# CH340T9R-R0.net
KiCad netlist of a schematic drawn in Altium Designer
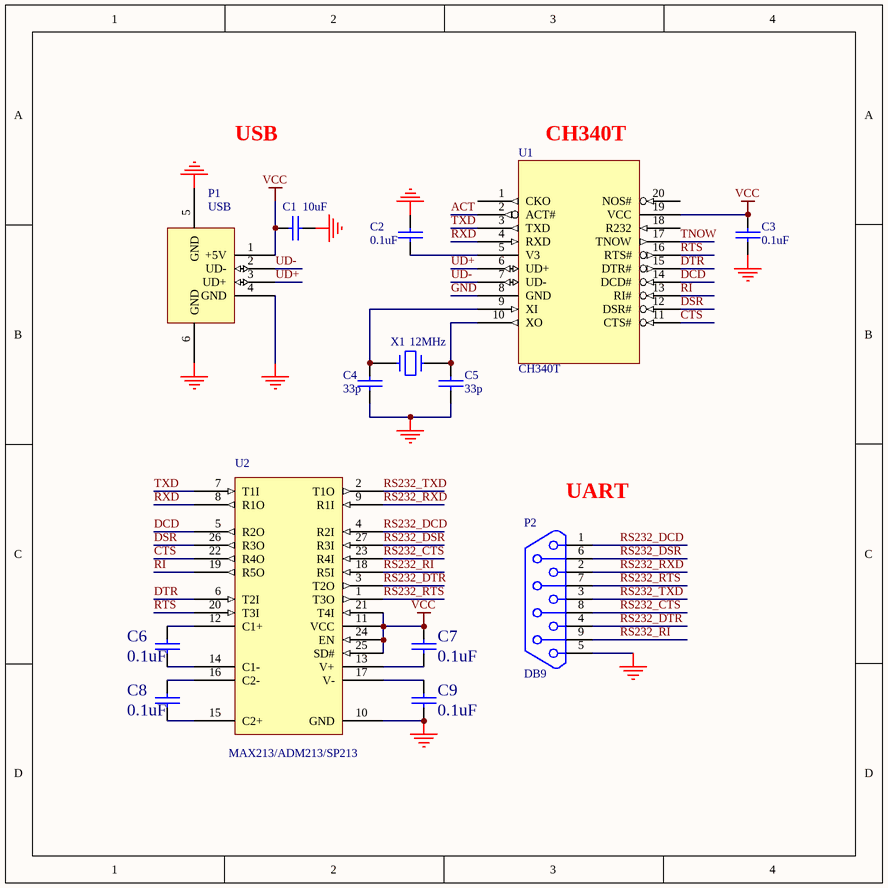
[diagram p0: CH340T9R-R0.SchDoc]

(export (version "E")
  (design (tool "Eeschema 10.0.6"))
  (components
    (comp (ref "C1")
      (value "10uF")
      (footprint "3216_C")
      (description "Capacitor")
      (libsource (lib "") (part "CAP_1"))
    )
    (comp (ref "C2")
      (value "0.1uF")
      (footprint "0603_C")
      (description "Capacitor")
      (libsource (lib "") (part "CAP_1"))
    )
    (comp (ref "C3")
      (value "0.1uF")
      (footprint "0603_C")
      (description "Capacitor")
      (libsource (lib "") (part "CAP_1"))
    )
    (comp (ref "C4")
      (value "33p")
      (footprint "0603_C")
      (description "Capacitor")
      (libsource (lib "*") (part "CAP"))
    )
    (comp (ref "C5")
      (value "33p")
      (footprint "0603_C")
      (description "Capacitor")
      (libsource (lib "*") (part "CAP"))
    )
    (comp (ref "C6")
      (value "0.1uF")
      (footprint "0603_C")
      (description "Capacitor")
      (libsource (lib "*") (part "CAP"))
    )
    (comp (ref "C7")
      (value "0.1uF")
      (footprint "0603_C")
      (description "Capacitor")
      (libsource (lib "*") (part "CAP"))
    )
    (comp (ref "C8")
      (value "0.1uF")
      (footprint "0603_C")
      (description "Capacitor")
      (libsource (lib "*") (part "CAP"))
    )
    (comp (ref "C9")
      (value "0.1uF")
      (footprint "0603_C")
      (description "Capacitor")
      (libsource (lib "*") (part "CAP"))
    )
    (comp (ref "P1") (value "USB") (footprint "USBAM") (libsource (lib "*") (part "USB")))
    (comp (ref "P2") (value "DB9") (footprint "DB9-PAD-M") (libsource (lib "*") (part "DB9")))
    (comp (ref "U1")
      (value "CH340T")
      (footprint "SSOP20")
      (description "USB to TTL Serial / UART,  USB to IrDA")
      (libsource (lib "CHXXX") (part "CH340T"))
    )
    (comp (ref "U2") (value "MAX213/ADM213/SP213") (footprint "SSOP28") (libsource (lib "*") (part "MAX213")))
    (comp (ref "X1")
      (value "12MHz")
      (footprint "XT3225")
      (description "Crystal")
      (libsource (lib "*") (part "CRYSTAL"))
    )
  )
  (nets
    (net (code "1") (name "/ACT") (class "Default")
      (node (ref "U1") (pin "2") (pinfunction "ACT#_2") (pintype "output"))
    )
    (net (code "2") (name "/CTS") (class "Default")
      (node (ref "U1") (pin "11") (pinfunction "CTS#_11") (pintype "input"))
      (node (ref "U2") (pin "22") (pinfunction "R4O_22") (pintype "output"))
    )
    (net (code "3") (name "/DCD") (class "Default")
      (node (ref "U1") (pin "14") (pinfunction "DCD#_14") (pintype "input"))
      (node (ref "U2") (pin "5") (pinfunction "R2O_5") (pintype "output"))
    )
    (net (code "4") (name "/DSR") (class "Default")
      (node (ref "U1") (pin "12") (pinfunction "DSR#_12") (pintype "input"))
      (node (ref "U2") (pin "26") (pinfunction "R3O_26") (pintype "output"))
    )
    (net (code "5") (name "/DTR") (class "Default")
      (node (ref "U1") (pin "15") (pinfunction "DTR#_15") (pintype "output"))
      (node (ref "U2") (pin "6") (pinfunction "T2I_6") (pintype "input"))
    )
    (net (code "6") (name "/RI") (class "Default")
      (node (ref "U1") (pin "13") (pinfunction "RI#_13") (pintype "input"))
      (node (ref "U2") (pin "19") (pinfunction "R5O_19") (pintype "output"))
    )
    (net (code "7") (name "/RS232_CTS") (class "Default")
      (node (ref "P2") (pin "8") (pinfunction "8_8") (pintype "passive"))
      (node (ref "U2") (pin "23") (pinfunction "R4I_23") (pintype "input"))
    )
    (net (code "8") (name "/RS232_DCD") (class "Default")
      (node (ref "P2") (pin "1") (pinfunction "1_1") (pintype "passive"))
      (node (ref "U2") (pin "4") (pinfunction "R2I_4") (pintype "input"))
    )
    (net (code "9") (name "/RS232_DSR") (class "Default")
      (node (ref "P2") (pin "6") (pinfunction "6_6") (pintype "passive"))
      (node (ref "U2") (pin "27") (pinfunction "R3I_27") (pintype "input"))
    )
    (net (code "10") (name "/RS232_DTR") (class "Default")
      (node (ref "P2") (pin "4") (pinfunction "4_4") (pintype "passive"))
      (node (ref "U2") (pin "3") (pinfunction "T2O_3") (pintype "output"))
    )
    (net (code "11") (name "/RS232_RI") (class "Default")
      (node (ref "P2") (pin "9") (pinfunction "9_9") (pintype "passive"))
      (node (ref "U2") (pin "18") (pinfunction "R5I_18") (pintype "input"))
    )
    (net (code "12") (name "/RS232_RTS") (class "Default")
      (node (ref "P2") (pin "7") (pinfunction "7_7") (pintype "passive"))
      (node (ref "U2") (pin "1") (pinfunction "T3O_1") (pintype "output"))
    )
    (net (code "13") (name "/RS232_RXD") (class "Default")
      (node (ref "P2") (pin "2") (pinfunction "2_2") (pintype "passive"))
      (node (ref "U2") (pin "9") (pinfunction "R1I_9") (pintype "input"))
    )
    (net (code "14") (name "/RS232_TXD") (class "Default")
      (node (ref "P2") (pin "3") (pinfunction "3_3") (pintype "passive"))
      (node (ref "U2") (pin "2") (pinfunction "T1O_2") (pintype "output"))
    )
    (net (code "15") (name "/RTS") (class "Default")
      (node (ref "U1") (pin "16") (pinfunction "RTS#_16") (pintype "output"))
      (node (ref "U2") (pin "20") (pinfunction "T3I_20") (pintype "input"))
    )
    (net (code "16") (name "/RXD") (class "Default")
      (node (ref "U1") (pin "4") (pinfunction "RXD_4") (pintype "input"))
      (node (ref "U2") (pin "8") (pinfunction "R1O_8") (pintype "output"))
    )
    (net (code "17") (name "/TNOW") (class "Default")
      (node (ref "U1") (pin "17") (pinfunction "TNOW_17") (pintype "output"))
    )
    (net (code "18") (name "/TXD") (class "Default")
      (node (ref "U1") (pin "3") (pinfunction "TXD_3") (pintype "output"))
      (node (ref "U2") (pin "7") (pinfunction "T1I_7") (pintype "input"))
    )
    (net (code "19") (name "/UD+") (class "Default")
      (node (ref "P1") (pin "3") (pinfunction "UD+_3") (pintype "bidirectional"))
      (node (ref "U1") (pin "6") (pinfunction "UD+_6") (pintype "bidirectional"))
    )
    (net (code "20") (name "/UD-") (class "Default")
      (node (ref "P1") (pin "2") (pinfunction "UD-_2") (pintype "bidirectional"))
      (node (ref "U1") (pin "7") (pinfunction "UD-_7") (pintype "bidirectional"))
    )
    (net (code "21") (name "GND") (class "Default")
      (node (ref "C1") (pin "2") (pinfunction "2_2") (pintype "passive"))
      (node (ref "C2") (pin "2") (pinfunction "2_2") (pintype "passive"))
      (node (ref "C3") (pin "2") (pinfunction "2_2") (pintype "passive"))
      (node (ref "C4") (pin "2") (pinfunction "2_2") (pintype "passive"))
      (node (ref "C5") (pin "2") (pinfunction "2_2") (pintype "passive"))
      (node (ref "C9") (pin "2") (pinfunction "2_2") (pintype "passive"))
      (node (ref "P1") (pin "4") (pinfunction "GND_4") (pintype "power_in"))
      (node (ref "P1") (pin "5") (pinfunction "GND_5") (pintype "power_in"))
      (node (ref "P1") (pin "6") (pinfunction "GND_6") (pintype "power_in"))
      (node (ref "P2") (pin "5") (pinfunction "5_5") (pintype "passive"))
      (node (ref "U1") (pin "8") (pinfunction "GND_8") (pintype "power_in"))
      (node (ref "U2") (pin "10") (pinfunction "GND_10") (pintype "power_in"))
    )
    (net (code "22") (name "Net-(U1-V3)") (class "Default")
      (node (ref "C2") (pin "1") (pinfunction "1_1") (pintype "passive"))
      (node (ref "U1") (pin "5") (pinfunction "V3_5") (pintype "power_in"))
    )
    (net (code "23") (name "Net-(U1-XI)") (class "Default")
      (node (ref "C4") (pin "1") (pinfunction "1_1") (pintype "passive"))
      (node (ref "U1") (pin "9") (pinfunction "XI_9") (pintype "input"))
      (node (ref "X1") (pin "1") (pinfunction "1_1") (pintype "passive"))
    )
    (net (code "24") (name "Net-(U1-XO)") (class "Default")
      (node (ref "C5") (pin "1") (pinfunction "1_1") (pintype "passive"))
      (node (ref "U1") (pin "10") (pinfunction "XO_10") (pintype "output"))
      (node (ref "X1") (pin "3") (pinfunction "3_3") (pintype "passive"))
    )
    (net (code "25") (name "Net-(U2-C1+)") (class "Default")
      (node (ref "C6") (pin "1") (pinfunction "1_1") (pintype "passive"))
      (node (ref "U2") (pin "12") (pinfunction "C1+_12") (pintype "passive"))
    )
    (net (code "26") (name "Net-(U2-C1-)") (class "Default")
      (node (ref "C6") (pin "2") (pinfunction "2_2") (pintype "passive"))
      (node (ref "U2") (pin "14") (pinfunction "C1-_14") (pintype "passive"))
    )
    (net (code "27") (name "Net-(U2-C2+)") (class "Default")
      (node (ref "C8") (pin "2") (pinfunction "2_2") (pintype "passive"))
      (node (ref "U2") (pin "15") (pinfunction "C2+_15") (pintype "passive"))
    )
    (net (code "28") (name "Net-(U2-C2-)") (class "Default")
      (node (ref "C8") (pin "1") (pinfunction "1_1") (pintype "passive"))
      (node (ref "U2") (pin "16") (pinfunction "C2-_16") (pintype "passive"))
    )
    (net (code "29") (name "Net-(U2-V+)") (class "Default")
      (node (ref "C7") (pin "2") (pinfunction "2_2") (pintype "passive"))
      (node (ref "U2") (pin "13") (pinfunction "V+_13") (pintype "passive"))
    )
    (net (code "30") (name "Net-(U2-V-)") (class "Default")
      (node (ref "C9") (pin "1") (pinfunction "1_1") (pintype "passive"))
      (node (ref "U2") (pin "17") (pinfunction "V-_17") (pintype "passive"))
    )
    (net (code "31") (name "VCC") (class "Default")
      (node (ref "C1") (pin "1") (pinfunction "1_1") (pintype "passive"))
      (node (ref "C3") (pin "1") (pinfunction "1_1") (pintype "passive"))
      (node (ref "C7") (pin "1") (pinfunction "1_1") (pintype "passive"))
      (node (ref "P1") (pin "1") (pinfunction "+5V_1") (pintype "power_in"))
      (node (ref "U1") (pin "19") (pinfunction "VCC_19") (pintype "power_in"))
      (node (ref "U2") (pin "11") (pinfunction "VCC_11") (pintype "power_in"))
      (node (ref "U2") (pin "21") (pinfunction "T4I_21") (pintype "input"))
      (node (ref "U2") (pin "24") (pinfunction "EN_24") (pintype "input"))
      (node (ref "U2") (pin "25") (pinfunction "SD#_25") (pintype "input"))
    )
    (net (code "32") (name "unconnected-(U1-CKO-Pad1)") (class "Default")
      (node (ref "U1") (pin "1") (pinfunction "CKO_1") (pintype "output"))
    )
    (net (code "33") (name "unconnected-(U1-NOS#-Pad20)") (class "Default")
      (node (ref "U1") (pin "20") (pinfunction "NOS#_20") (pintype "input"))
    )
    (net (code "34") (name "unconnected-(U1-R232-Pad18)") (class "Default")
      (node (ref "U1") (pin "18") (pinfunction "R232_18") (pintype "input"))
    )
  )
)
